# kuafu02_NI.net
KiCad netlist of a schematic drawn in EasyEDA Pro
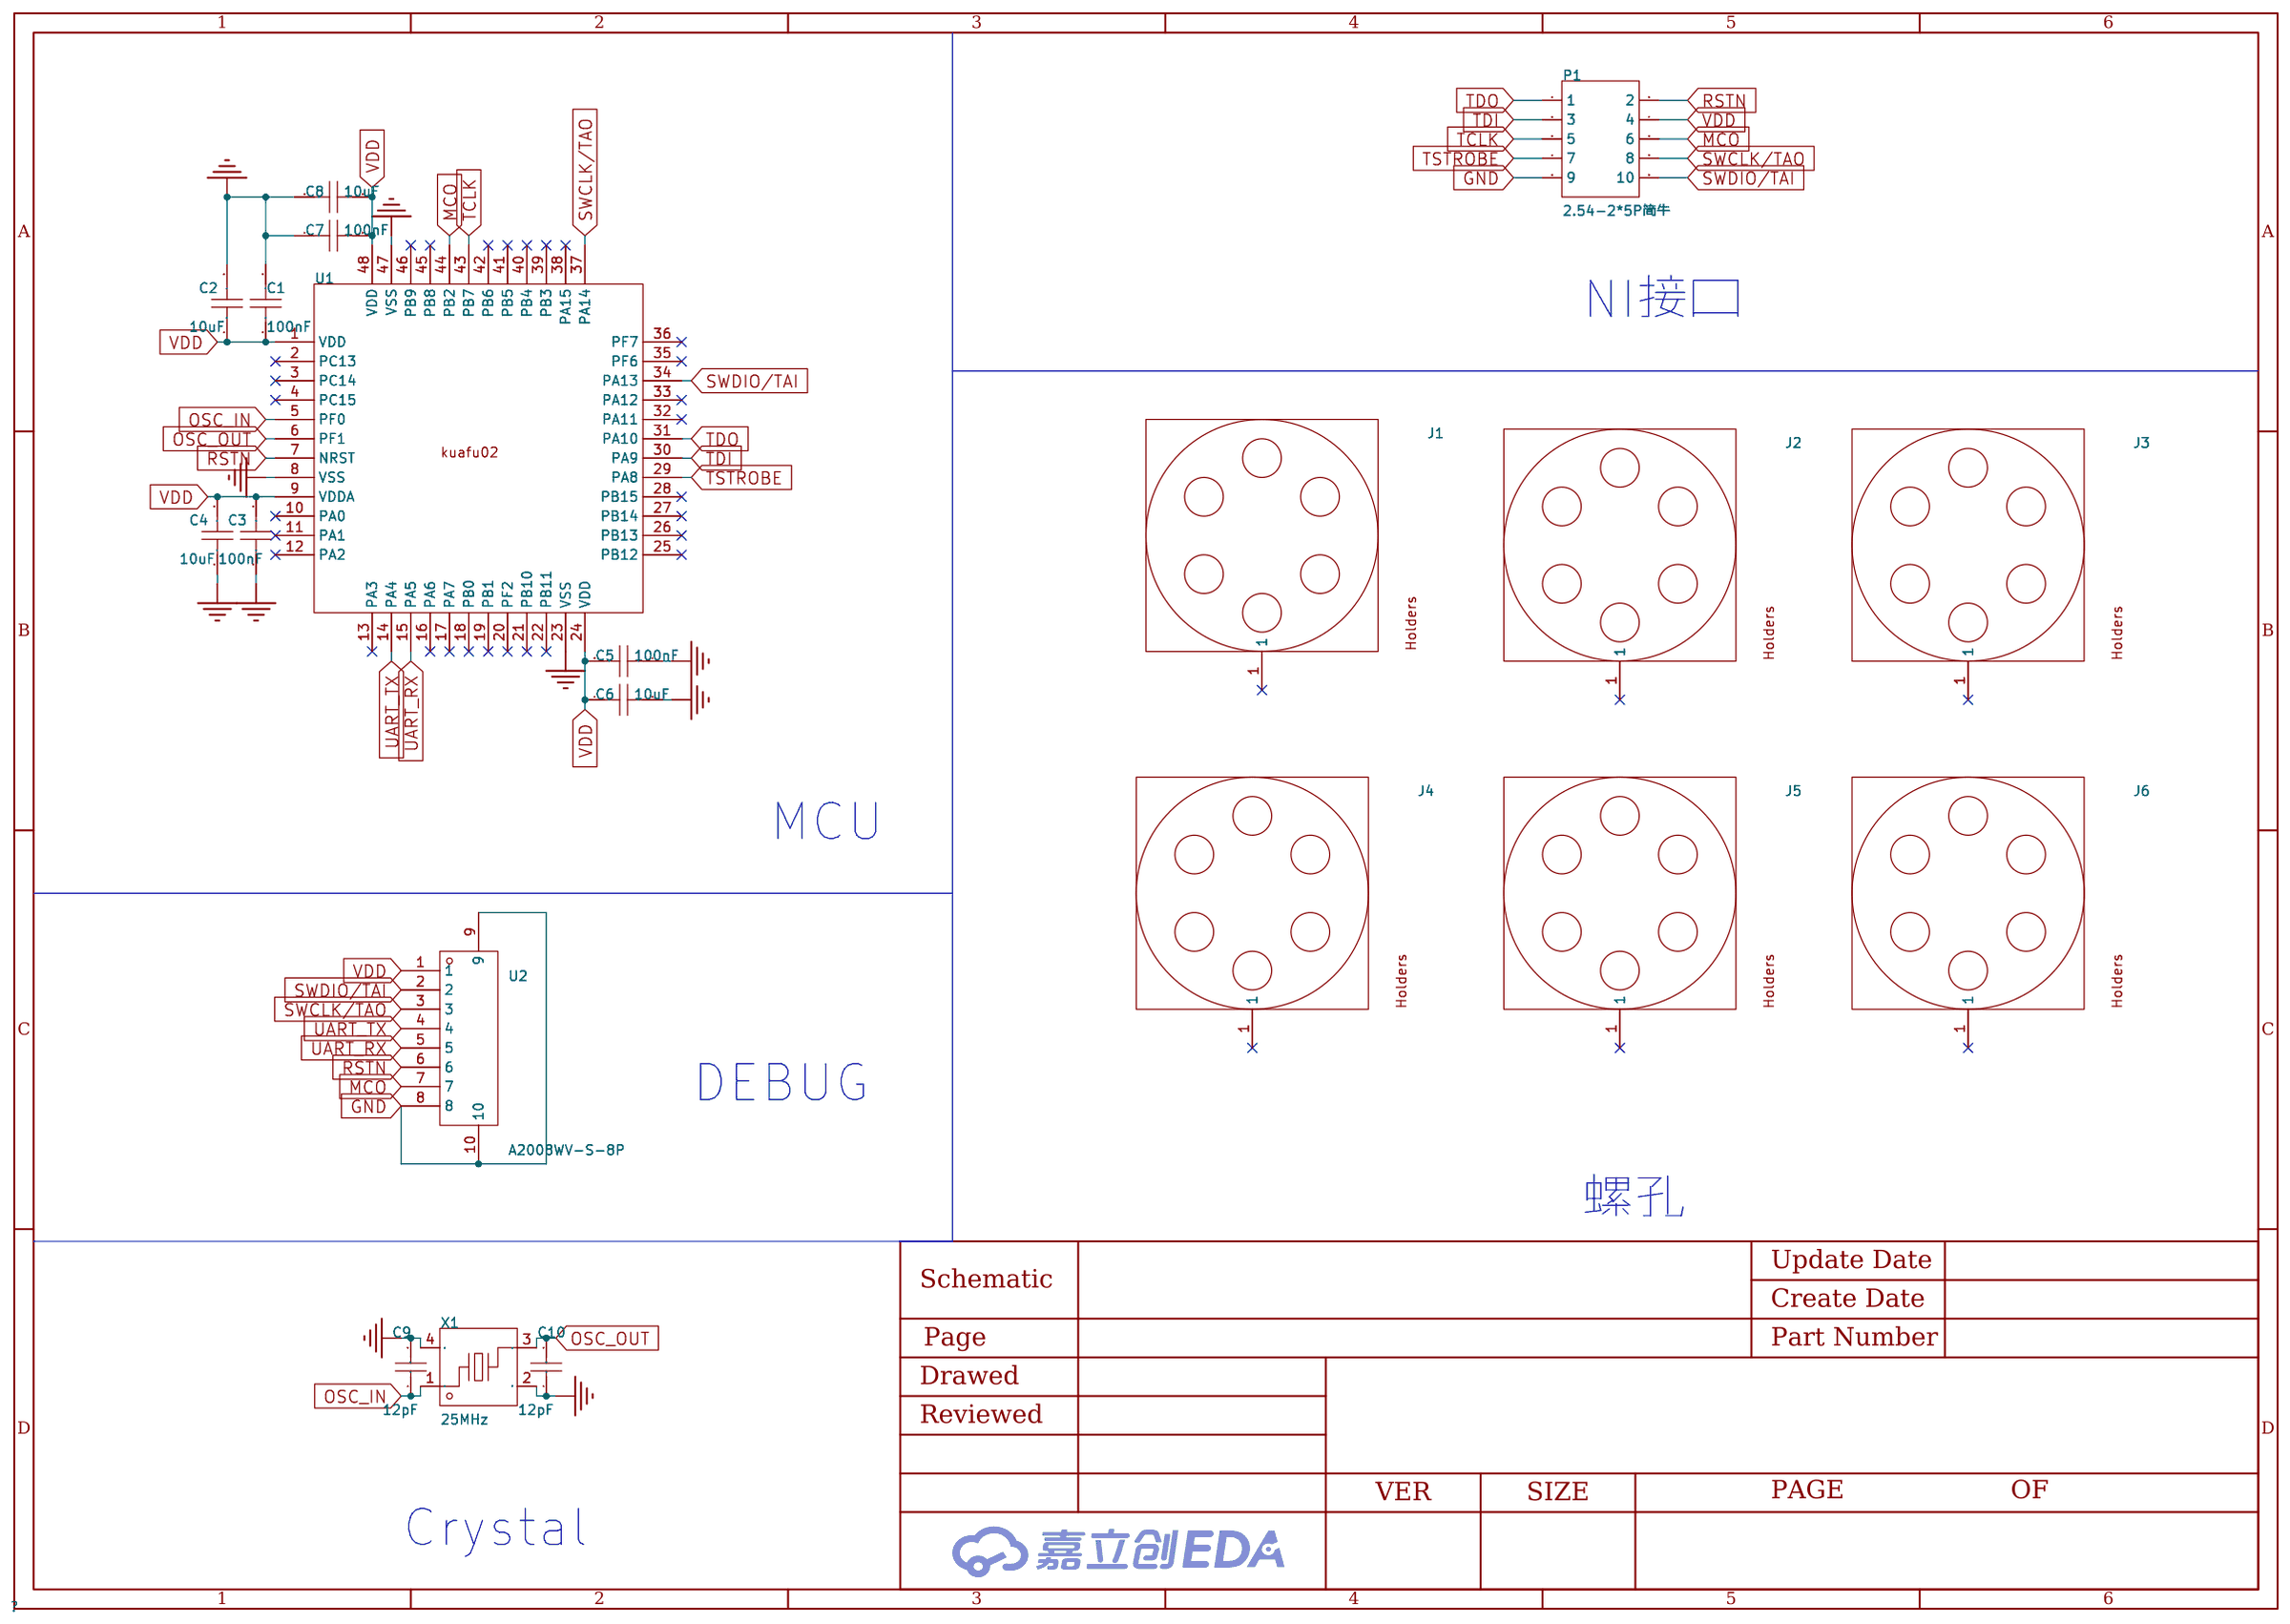
[diagram p0: schematic sheet]

(export (version "E")
  (design (tool "Eeschema 10.0.6"))
  (components
    (comp (ref "C1")
      (value "100nF")
      (footprint "easyedapro:C0603")
      (description "容值:100nF;精度:±10%;额定电压:50V;材质(温度系数):X7R;")
      (fields
        (field (name "Manufacturer Part") "CC0603KRX7R9BB104")
        (field (name "Manufacturer") "YAGEO(国巨)")
      )
      (libsource (lib "easyedapro") (part "CC0603KRX7R9BB104"))
    )
    (comp (ref "C2")
      (value "10uF")
      (footprint "easyedapro:C0603")
      (description "容值:10uF;精度:±10%;额定电压:10V;材质(温度系数):X5R;")
      (fields
        (field (name "Manufacturer Part") "CL10A106KP8NNNC")
        (field (name "Manufacturer") "SAMSUNG(三星)")
      )
      (libsource (lib "easyedapro") (part "CL10A106KP8NNNC"))
    )
    (comp (ref "C3")
      (value "100nF")
      (footprint "easyedapro:C0603")
      (description "容值:100nF;精度:±10%;额定电压:50V;材质(温度系数):X7R;")
      (fields
        (field (name "Manufacturer Part") "CC0603KRX7R9BB104")
        (field (name "Manufacturer") "YAGEO(国巨)")
      )
      (libsource (lib "easyedapro") (part "CC0603KRX7R9BB104"))
    )
    (comp (ref "C4")
      (value "10uF")
      (footprint "easyedapro:C0603")
      (description "容值:10uF;精度:±10%;额定电压:10V;材质(温度系数):X5R;")
      (fields
        (field (name "Manufacturer Part") "CL10A106KP8NNNC")
        (field (name "Manufacturer") "SAMSUNG(三星)")
      )
      (libsource (lib "easyedapro") (part "CL10A106KP8NNNC"))
    )
    (comp (ref "C5")
      (value "100nF")
      (footprint "easyedapro:C0603")
      (description "容值:100nF;精度:±10%;额定电压:50V;材质(温度系数):X7R;")
      (fields
        (field (name "Manufacturer Part") "CC0603KRX7R9BB104")
        (field (name "Manufacturer") "YAGEO(国巨)")
      )
      (libsource (lib "easyedapro") (part "CC0603KRX7R9BB104"))
    )
    (comp (ref "C6")
      (value "10uF")
      (footprint "easyedapro:C0603")
      (description "容值:10uF;精度:±10%;额定电压:10V;材质(温度系数):X5R;")
      (fields
        (field (name "Manufacturer Part") "CL10A106KP8NNNC")
        (field (name "Manufacturer") "SAMSUNG(三星)")
      )
      (libsource (lib "easyedapro") (part "CL10A106KP8NNNC"))
    )
    (comp (ref "C7")
      (value "100nF")
      (footprint "easyedapro:C0603")
      (description "容值:100nF;精度:±10%;额定电压:50V;材质(温度系数):X7R;")
      (fields
        (field (name "Manufacturer Part") "CC0603KRX7R9BB104")
        (field (name "Manufacturer") "YAGEO(国巨)")
      )
      (libsource (lib "easyedapro") (part "CC0603KRX7R9BB104"))
    )
    (comp (ref "C8")
      (value "10uF")
      (footprint "easyedapro:C0603")
      (description "容值:10uF;精度:±10%;额定电压:10V;材质(温度系数):X5R;")
      (fields
        (field (name "Manufacturer Part") "CL10A106KP8NNNC")
        (field (name "Manufacturer") "SAMSUNG(三星)")
      )
      (libsource (lib "easyedapro") (part "CL10A106KP8NNNC"))
    )
    (comp (ref "C9")
      (value "12pF")
      (footprint "easyedapro:C0603")
      (description "容值:12pF;精度:±5%;额定电压:50V;材质(温度系数):C0G;")
      (fields
        (field (name "Manufacturer Part") "CL10C120JB8NNNC")
        (field (name "Manufacturer") "SAMSUNG(三星)")
      )
      (libsource (lib "easyedapro") (part "CL10C120JB8NNNC"))
    )
    (comp (ref "C10")
      (value "12pF")
      (footprint "easyedapro:C0603")
      (description "容值:12pF;精度:±5%;额定电压:50V;材质(温度系数):C0G;")
      (fields
        (field (name "Manufacturer Part") "CL10C120JB8NNNC")
        (field (name "Manufacturer") "SAMSUNG(三星)")
      )
      (libsource (lib "easyedapro") (part "CL10C120JB8NNNC"))
    )
    (comp (ref "J1")
      (value "~")
      (footprint "easyedapro:DEMO板安装孔")
      (libsource (lib "easyedapro") (part "螺孔_3.1X6MM"))
    )
    (comp (ref "J2")
      (value "~")
      (footprint "easyedapro:DEMO板安装孔")
      (libsource (lib "easyedapro") (part "螺孔_3.1X6MM"))
    )
    (comp (ref "J3")
      (value "~")
      (footprint "easyedapro:DEMO板安装孔")
      (libsource (lib "easyedapro") (part "螺孔_3.1X6MM"))
    )
    (comp (ref "J4")
      (value "~")
      (footprint "easyedapro:DEMO板安装孔")
      (libsource (lib "easyedapro") (part "螺孔_3.1X6MM"))
    )
    (comp (ref "J5")
      (value "~")
      (footprint "easyedapro:DEMO板安装孔")
      (libsource (lib "easyedapro") (part "螺孔_3.1X6MM"))
    )
    (comp (ref "J6")
      (value "~")
      (footprint "easyedapro:DEMO板安装孔")
      (libsource (lib "easyedapro") (part "螺孔_3.1X6MM"))
    )
    (comp (ref "P1")
      (value "2.54-2*5P简牛")
      (footprint "easyedapro:IDC-TH_10P-P2.54_C5665")
      (description "连接器类型:简牛座;每排PIN数:5;排数:2;间距:2.54mm;行距:2.54mm;封装形式:直插;触头材质:-;触头镀层:-;")
      (fields (field (name "Manufacturer") "BOOMELE(博穆精密)"))
      (libsource (lib "easyedapro") (part "HDR-IDC-2.54-2X5P"))
    )
    (comp (ref "U1")
      (value "~")
      (footprint "easyedapro:LQFP-48_L7.0-W7.0-P0.50-LS9.0-BL")
      (libsource (lib "easyedapro") (part "kuafu02"))
    )
    (comp (ref "U2")
      (value "A2008WV-S-8P")
      (footprint "easyedapro:CONN-SMD_A2008WV-S-8P")
      (description "参考系列:PH;间距:2mm;插针结构:1x8P;排数:1;每排PIN数:8;行距:-;安装方式:-;触头材质:黄铜;")
      (fields (field (name "Manufacturer") "CJT(长江连接器)"))
      (libsource (lib "easyedapro") (part "A2008WV-S-8P"))
    )
    (comp (ref "X1")
      (value "25MHz")
      (footprint "easyedapro:CRYSTAL-SMD_4P-L3.2-W2.5-BL")
      (description "频率:25MHz;频率公差:10ppm;负载电容:12pF;")
      (fields
        (field (name "Manufacturer Part") "XC322525MOB4SA-18")
        (field (name "Manufacturer") "YXC(扬兴晶振)")
      )
      (libsource (lib "easyedapro") (part "XC322525MOB4SA-18"))
    )
  )
  (nets
    (net (code "1") (name "GND") (class "Default")
      (node (ref "C1") (pin "2") (pinfunction "2_2") (pintype "input"))
      (node (ref "C10") (pin "1") (pinfunction "1_1") (pintype "input"))
      (node (ref "C2") (pin "2") (pinfunction "2_2") (pintype "input"))
      (node (ref "C3") (pin "1") (pinfunction "1_1") (pintype "input"))
      (node (ref "C4") (pin "1") (pinfunction "1_1") (pintype "input"))
      (node (ref "C5") (pin "1") (pinfunction "1_1") (pintype "input"))
      (node (ref "C6") (pin "2") (pinfunction "2_2") (pintype "input"))
      (node (ref "C7") (pin "1") (pinfunction "1_1") (pintype "input"))
      (node (ref "C8") (pin "2") (pinfunction "2_2") (pintype "input"))
      (node (ref "C9") (pin "2") (pinfunction "2_2") (pintype "input"))
      (node (ref "P1") (pin "9") (pinfunction "9_9") (pintype "input"))
      (node (ref "U1") (pin "23") (pinfunction "VSS_23") (pintype "input"))
      (node (ref "U1") (pin "47") (pinfunction "VSS_47") (pintype "input"))
      (node (ref "U1") (pin "8") (pinfunction "VSS_8") (pintype "input"))
      (node (ref "U2") (pin "10") (pinfunction "10_10") (pintype "input"))
      (node (ref "U2") (pin "8") (pinfunction "8_8") (pintype "input"))
      (node (ref "U2") (pin "9") (pinfunction "9_9") (pintype "input"))
      (node (ref "X1") (pin "2") (pinfunction "GND_2") (pintype "input"))
      (node (ref "X1") (pin "4") (pinfunction "GND_4") (pintype "input"))
    )
    (net (code "2") (name "MCO") (class "Default")
      (node (ref "P1") (pin "6") (pinfunction "6_6") (pintype "input"))
      (node (ref "U1") (pin "44") (pinfunction "PB2_44") (pintype "input"))
      (node (ref "U2") (pin "7") (pinfunction "7_7") (pintype "input"))
    )
    (net (code "3") (name "OSC_IN") (class "Default")
      (node (ref "C9") (pin "1") (pinfunction "1_1") (pintype "input"))
      (node (ref "U1") (pin "5") (pinfunction "PF0_5") (pintype "input"))
      (node (ref "X1") (pin "1") (pinfunction "1_1") (pintype "input"))
    )
    (net (code "4") (name "OSC_OUT") (class "Default")
      (node (ref "C10") (pin "2") (pinfunction "2_2") (pintype "input"))
      (node (ref "U1") (pin "6") (pinfunction "PF1_6") (pintype "input"))
      (node (ref "X1") (pin "3") (pinfunction "3_3") (pintype "input"))
    )
    (net (code "5") (name "RSTN") (class "Default")
      (node (ref "P1") (pin "2") (pinfunction "2_2") (pintype "input"))
      (node (ref "U1") (pin "7") (pinfunction "NRST_7") (pintype "input"))
      (node (ref "U2") (pin "6") (pinfunction "6_6") (pintype "input"))
    )
    (net (code "6") (name "SWCLK{slash}TAO") (class "Default")
      (node (ref "P1") (pin "8") (pinfunction "8_8") (pintype "input"))
      (node (ref "U1") (pin "37") (pinfunction "PA14_37") (pintype "input"))
      (node (ref "U2") (pin "3") (pinfunction "3_3") (pintype "input"))
    )
    (net (code "7") (name "SWDIO{slash}TAI") (class "Default")
      (node (ref "P1") (pin "10") (pinfunction "10_10") (pintype "input"))
      (node (ref "U1") (pin "34") (pinfunction "PA13_34") (pintype "input"))
      (node (ref "U2") (pin "2") (pinfunction "2_2") (pintype "input"))
    )
    (net (code "8") (name "TCLK") (class "Default")
      (node (ref "P1") (pin "5") (pinfunction "5_5") (pintype "input"))
      (node (ref "U1") (pin "43") (pinfunction "PB7_43") (pintype "input"))
    )
    (net (code "9") (name "TDI") (class "Default")
      (node (ref "P1") (pin "3") (pinfunction "3_3") (pintype "input"))
      (node (ref "U1") (pin "30") (pinfunction "PA9_30") (pintype "input"))
    )
    (net (code "10") (name "TDO") (class "Default")
      (node (ref "P1") (pin "1") (pinfunction "1_1") (pintype "input"))
      (node (ref "U1") (pin "31") (pinfunction "PA10_31") (pintype "input"))
    )
    (net (code "11") (name "TSTROBE") (class "Default")
      (node (ref "P1") (pin "7") (pinfunction "7_7") (pintype "input"))
      (node (ref "U1") (pin "29") (pinfunction "PA8_29") (pintype "input"))
    )
    (net (code "12") (name "UART_RX") (class "Default")
      (node (ref "U1") (pin "15") (pinfunction "PA5_15") (pintype "input"))
      (node (ref "U2") (pin "5") (pinfunction "5_5") (pintype "input"))
    )
    (net (code "13") (name "UART_TX") (class "Default")
      (node (ref "U1") (pin "14") (pinfunction "PA4_14") (pintype "input"))
      (node (ref "U2") (pin "4") (pinfunction "4_4") (pintype "input"))
    )
    (net (code "14") (name "VDD") (class "Default")
      (node (ref "C1") (pin "1") (pinfunction "1_1") (pintype "input"))
      (node (ref "C2") (pin "1") (pinfunction "1_1") (pintype "input"))
      (node (ref "C3") (pin "2") (pinfunction "2_2") (pintype "input"))
      (node (ref "C4") (pin "2") (pinfunction "2_2") (pintype "input"))
      (node (ref "C5") (pin "2") (pinfunction "2_2") (pintype "input"))
      (node (ref "C6") (pin "1") (pinfunction "1_1") (pintype "input"))
      (node (ref "C7") (pin "2") (pinfunction "2_2") (pintype "input"))
      (node (ref "C8") (pin "1") (pinfunction "1_1") (pintype "input"))
      (node (ref "P1") (pin "4") (pinfunction "4_4") (pintype "input"))
      (node (ref "U1") (pin "1") (pinfunction "VDD_1") (pintype "input"))
      (node (ref "U1") (pin "24") (pinfunction "VDD_24") (pintype "input"))
      (node (ref "U1") (pin "48") (pinfunction "VDD_48") (pintype "input"))
      (node (ref "U1") (pin "9") (pinfunction "VDDA_9") (pintype "input"))
      (node (ref "U2") (pin "1") (pinfunction "1_1") (pintype "input"))
    )
    (net (code "15") (name "unconnected-(J1-Pad1)") (class "Default")
      (node (ref "J1") (pin "1") (pinfunction "1_1") (pintype "input+no_connect"))
    )
    (net (code "16") (name "unconnected-(J2-Pad1)") (class "Default")
      (node (ref "J2") (pin "1") (pinfunction "1_1") (pintype "input+no_connect"))
    )
    (net (code "17") (name "unconnected-(J3-Pad1)") (class "Default")
      (node (ref "J3") (pin "1") (pinfunction "1_1") (pintype "input+no_connect"))
    )
    (net (code "18") (name "unconnected-(J4-Pad1)") (class "Default")
      (node (ref "J4") (pin "1") (pinfunction "1_1") (pintype "input+no_connect"))
    )
    (net (code "19") (name "unconnected-(J5-Pad1)") (class "Default")
      (node (ref "J5") (pin "1") (pinfunction "1_1") (pintype "input+no_connect"))
    )
    (net (code "20") (name "unconnected-(J6-Pad1)") (class "Default")
      (node (ref "J6") (pin "1") (pinfunction "1_1") (pintype "input+no_connect"))
    )
    (net (code "21") (name "unconnected-(U1-PA0-Pad10)") (class "Default")
      (node (ref "U1") (pin "10") (pinfunction "PA0_10") (pintype "input+no_connect"))
    )
    (net (code "22") (name "unconnected-(U1-PA1-Pad11)") (class "Default")
      (node (ref "U1") (pin "11") (pinfunction "PA1_11") (pintype "input+no_connect"))
    )
    (net (code "23") (name "unconnected-(U1-PA2-Pad12)") (class "Default")
      (node (ref "U1") (pin "12") (pinfunction "PA2_12") (pintype "input+no_connect"))
    )
    (net (code "24") (name "unconnected-(U1-PA3-Pad13)") (class "Default")
      (node (ref "U1") (pin "13") (pinfunction "PA3_13") (pintype "input+no_connect"))
    )
    (net (code "25") (name "unconnected-(U1-PA6-Pad16)") (class "Default")
      (node (ref "U1") (pin "16") (pinfunction "PA6_16") (pintype "input+no_connect"))
    )
    (net (code "26") (name "unconnected-(U1-PA7-Pad17)") (class "Default")
      (node (ref "U1") (pin "17") (pinfunction "PA7_17") (pintype "input+no_connect"))
    )
    (net (code "27") (name "unconnected-(U1-PA11-Pad32)") (class "Default")
      (node (ref "U1") (pin "32") (pinfunction "PA11_32") (pintype "input+no_connect"))
    )
    (net (code "28") (name "unconnected-(U1-PA12-Pad33)") (class "Default")
      (node (ref "U1") (pin "33") (pinfunction "PA12_33") (pintype "input+no_connect"))
    )
    (net (code "29") (name "unconnected-(U1-PA15-Pad38)") (class "Default")
      (node (ref "U1") (pin "38") (pinfunction "PA15_38") (pintype "input+no_connect"))
    )
    (net (code "30") (name "unconnected-(U1-PB0-Pad18)") (class "Default")
      (node (ref "U1") (pin "18") (pinfunction "PB0_18") (pintype "input+no_connect"))
    )
    (net (code "31") (name "unconnected-(U1-PB1-Pad19)") (class "Default")
      (node (ref "U1") (pin "19") (pinfunction "PB1_19") (pintype "input+no_connect"))
    )
    (net (code "32") (name "unconnected-(U1-PB3-Pad39)") (class "Default")
      (node (ref "U1") (pin "39") (pinfunction "PB3_39") (pintype "input+no_connect"))
    )
    (net (code "33") (name "unconnected-(U1-PB4-Pad40)") (class "Default")
      (node (ref "U1") (pin "40") (pinfunction "PB4_40") (pintype "input+no_connect"))
    )
    (net (code "34") (name "unconnected-(U1-PB5-Pad41)") (class "Default")
      (node (ref "U1") (pin "41") (pinfunction "PB5_41") (pintype "input+no_connect"))
    )
    (net (code "35") (name "unconnected-(U1-PB6-Pad42)") (class "Default")
      (node (ref "U1") (pin "42") (pinfunction "PB6_42") (pintype "input+no_connect"))
    )
    (net (code "36") (name "unconnected-(U1-PB8-Pad45)") (class "Default")
      (node (ref "U1") (pin "45") (pinfunction "PB8_45") (pintype "input+no_connect"))
    )
    (net (code "37") (name "unconnected-(U1-PB9-Pad46)") (class "Default")
      (node (ref "U1") (pin "46") (pinfunction "PB9_46") (pintype "input+no_connect"))
    )
    (net (code "38") (name "unconnected-(U1-PB10-Pad21)") (class "Default")
      (node (ref "U1") (pin "21") (pinfunction "PB10_21") (pintype "input+no_connect"))
    )
    (net (code "39") (name "unconnected-(U1-PB11-Pad22)") (class "Default")
      (node (ref "U1") (pin "22") (pinfunction "PB11_22") (pintype "input+no_connect"))
    )
    (net (code "40") (name "unconnected-(U1-PB12-Pad25)") (class "Default")
      (node (ref "U1") (pin "25") (pinfunction "PB12_25") (pintype "input+no_connect"))
    )
    (net (code "41") (name "unconnected-(U1-PB13-Pad26)") (class "Default")
      (node (ref "U1") (pin "26") (pinfunction "PB13_26") (pintype "input+no_connect"))
    )
    (net (code "42") (name "unconnected-(U1-PB14-Pad27)") (class "Default")
      (node (ref "U1") (pin "27") (pinfunction "PB14_27") (pintype "input+no_connect"))
    )
    (net (code "43") (name "unconnected-(U1-PB15-Pad28)") (class "Default")
      (node (ref "U1") (pin "28") (pinfunction "PB15_28") (pintype "input+no_connect"))
    )
    (net (code "44") (name "unconnected-(U1-PC13-Pad2)") (class "Default")
      (node (ref "U1") (pin "2") (pinfunction "PC13_2") (pintype "input+no_connect"))
    )
    (net (code "45") (name "unconnected-(U1-PC14-Pad3)") (class "Default")
      (node (ref "U1") (pin "3") (pinfunction "PC14_3") (pintype "input+no_connect"))
    )
    (net (code "46") (name "unconnected-(U1-PC15-Pad4)") (class "Default")
      (node (ref "U1") (pin "4") (pinfunction "PC15_4") (pintype "input+no_connect"))
    )
    (net (code "47") (name "unconnected-(U1-PF2-Pad20)") (class "Default")
      (node (ref "U1") (pin "20") (pinfunction "PF2_20") (pintype "input+no_connect"))
    )
    (net (code "48") (name "unconnected-(U1-PF6-Pad35)") (class "Default")
      (node (ref "U1") (pin "35") (pinfunction "PF6_35") (pintype "input+no_connect"))
    )
    (net (code "49") (name "unconnected-(U1-PF7-Pad36)") (class "Default")
      (node (ref "U1") (pin "36") (pinfunction "PF7_36") (pintype "input+no_connect"))
    )
  )
)
